# sch2.net
KiCad netlist of a schematic drawn in Altium Designer
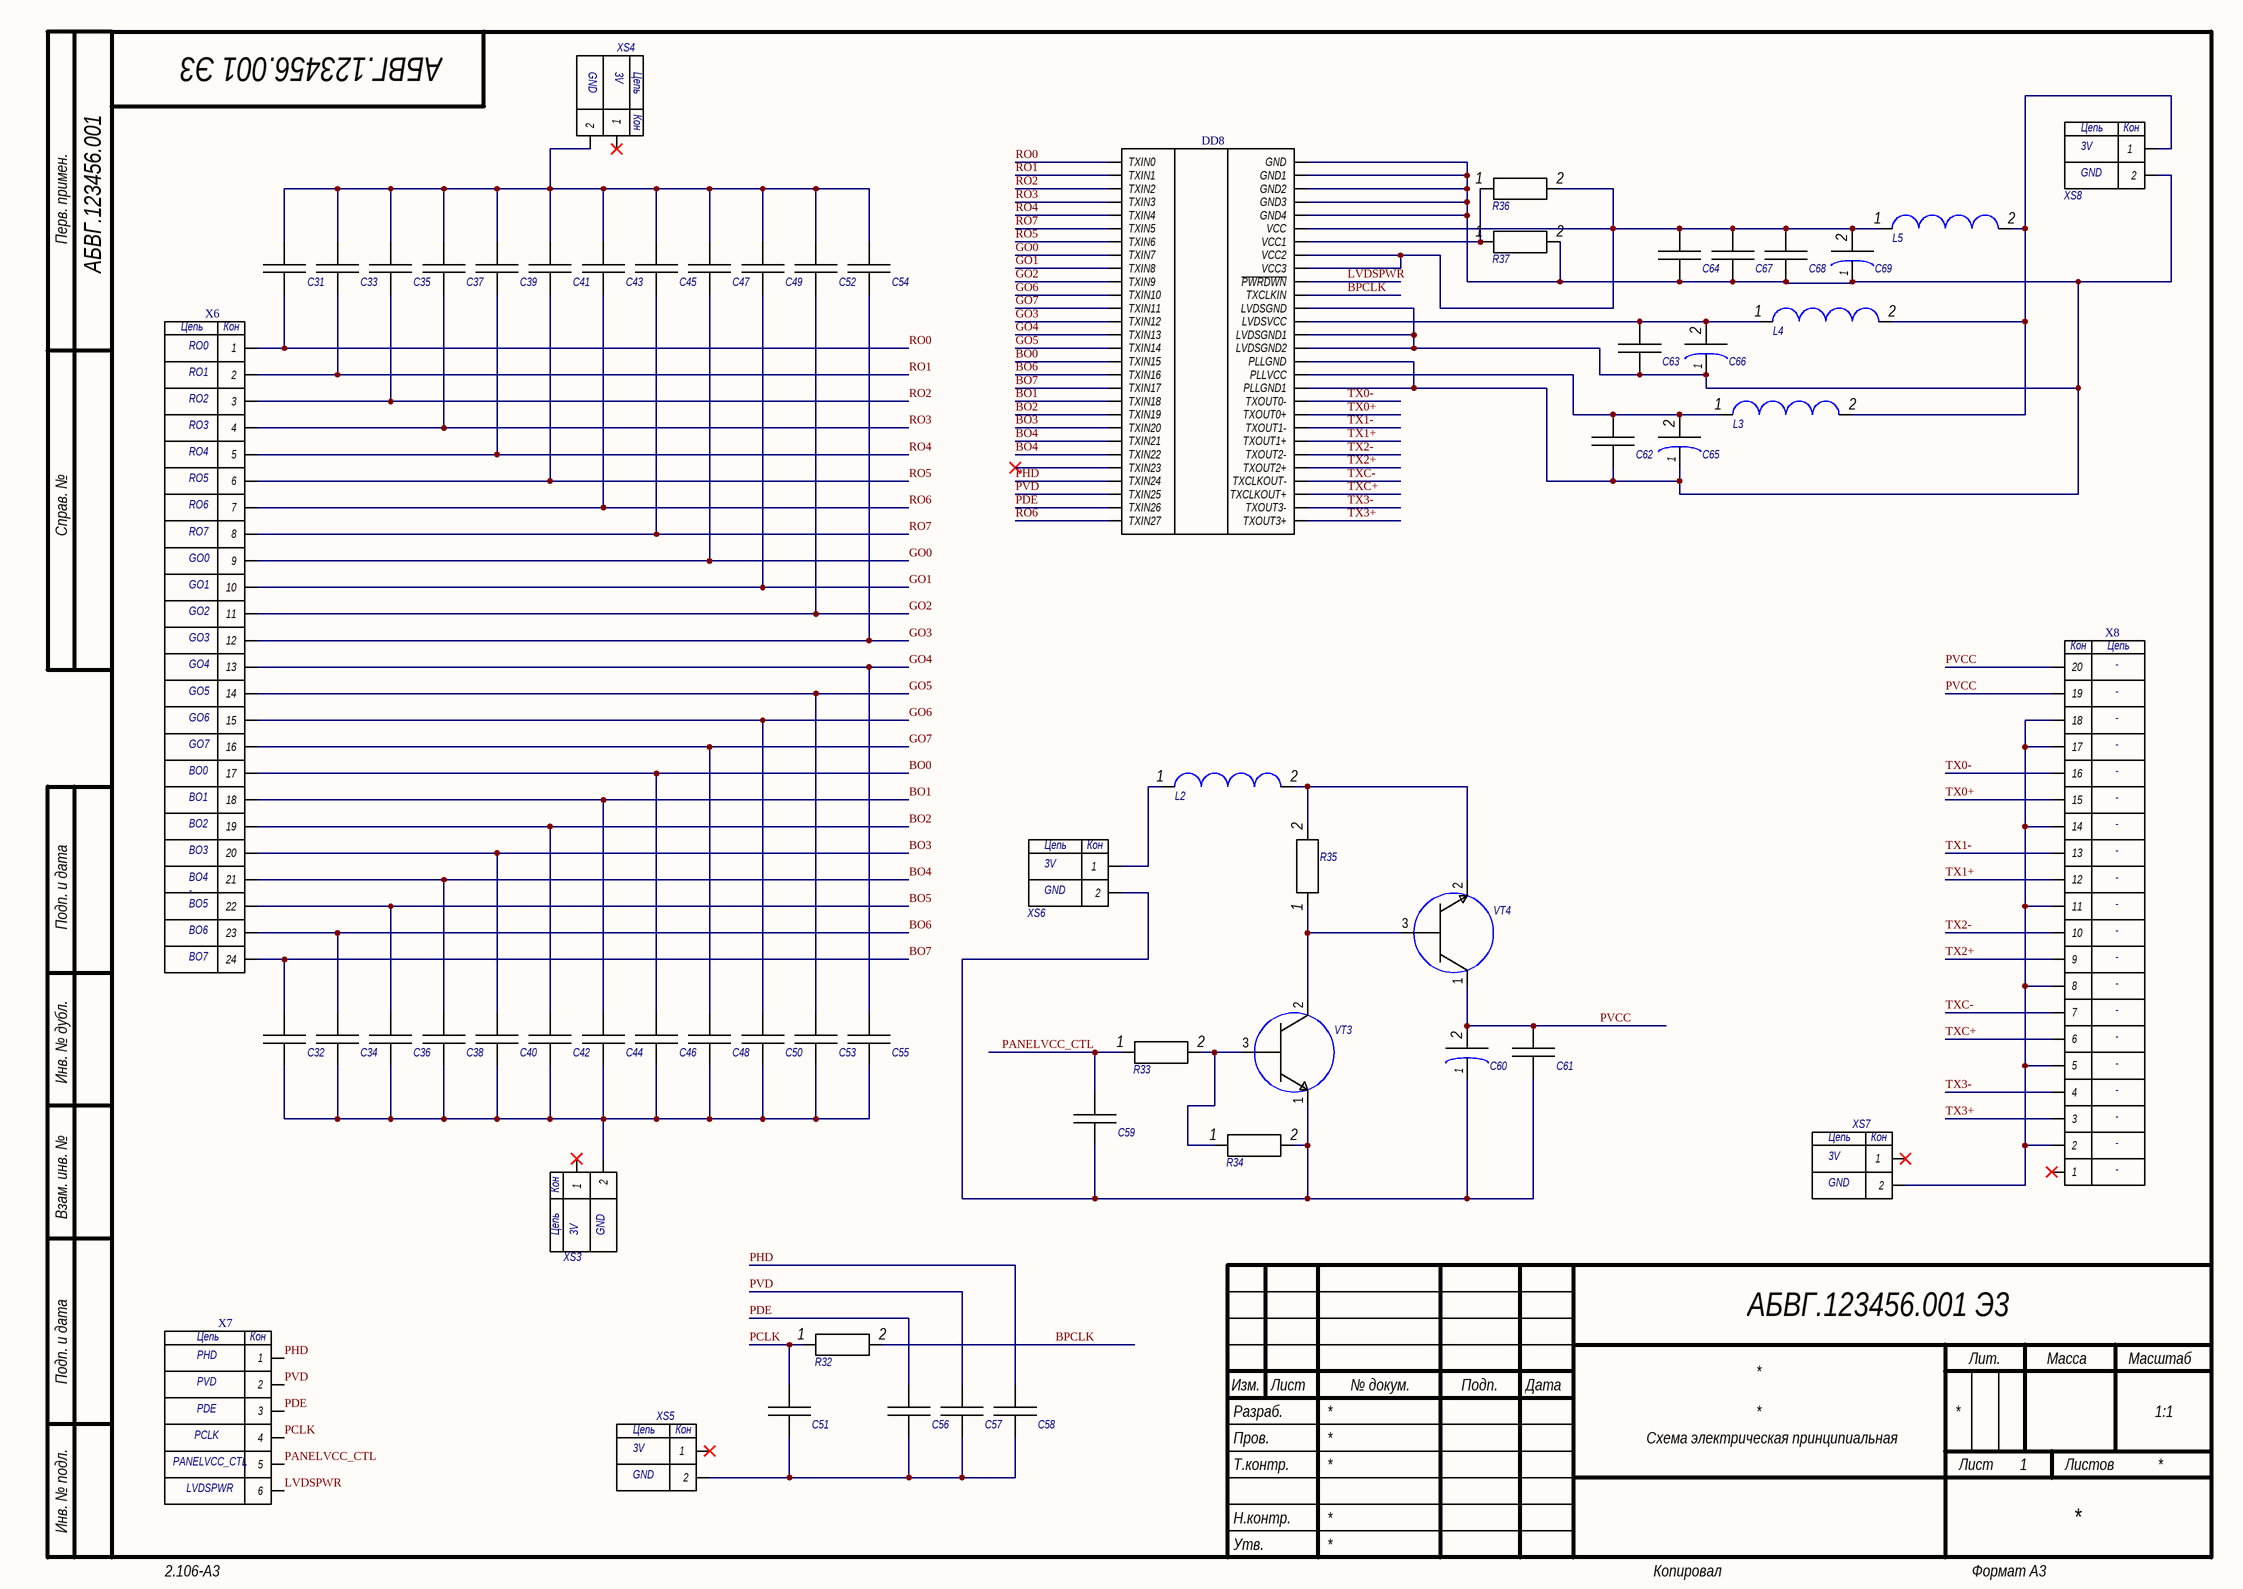
[diagram p0: sch2.SchDoc]

(export (version "E")
  (design (tool "Eeschema 10.0.6"))
  (components
    (comp (ref "C31")
      (value "Capacitor")
      (footprint "cap(0603)")
      (libsource (lib "sk7shared") (part "Capacitor"))
    )
    (comp (ref "C32")
      (value "Capacitor")
      (footprint "cap(0603)")
      (libsource (lib "sk7shared") (part "Capacitor"))
    )
    (comp (ref "C33")
      (value "Capacitor")
      (footprint "cap(0603)")
      (libsource (lib "sk7shared") (part "Capacitor"))
    )
    (comp (ref "C34")
      (value "Capacitor")
      (footprint "cap(0603)")
      (libsource (lib "sk7shared") (part "Capacitor"))
    )
    (comp (ref "C35")
      (value "Capacitor")
      (footprint "cap(0603)")
      (libsource (lib "sk7shared") (part "Capacitor"))
    )
    (comp (ref "C36")
      (value "Capacitor")
      (footprint "cap(0603)")
      (libsource (lib "sk7shared") (part "Capacitor"))
    )
    (comp (ref "C37")
      (value "Capacitor")
      (footprint "cap(0603)")
      (libsource (lib "sk7shared") (part "Capacitor"))
    )
    (comp (ref "C38")
      (value "Capacitor")
      (footprint "cap(0603)")
      (libsource (lib "sk7shared") (part "Capacitor"))
    )
    (comp (ref "C39")
      (value "Capacitor")
      (footprint "cap(0603)")
      (libsource (lib "sk7shared") (part "Capacitor"))
    )
    (comp (ref "C40")
      (value "Capacitor")
      (footprint "cap(0603)")
      (libsource (lib "sk7shared") (part "Capacitor"))
    )
    (comp (ref "C41")
      (value "Capacitor")
      (footprint "cap(0603)")
      (libsource (lib "sk7shared") (part "Capacitor"))
    )
    (comp (ref "C42")
      (value "Capacitor")
      (footprint "cap(0603)")
      (libsource (lib "sk7shared") (part "Capacitor"))
    )
    (comp (ref "C43")
      (value "Capacitor")
      (footprint "cap(0603)")
      (libsource (lib "sk7shared") (part "Capacitor"))
    )
    (comp (ref "C44")
      (value "Capacitor")
      (footprint "cap(0603)")
      (libsource (lib "sk7shared") (part "Capacitor"))
    )
    (comp (ref "C45")
      (value "Capacitor")
      (footprint "cap(0603)")
      (libsource (lib "sk7shared") (part "Capacitor"))
    )
    (comp (ref "C46")
      (value "Capacitor")
      (footprint "cap(0603)")
      (libsource (lib "sk7shared") (part "Capacitor"))
    )
    (comp (ref "C47")
      (value "Capacitor")
      (footprint "cap(0603)")
      (libsource (lib "sk7shared") (part "Capacitor"))
    )
    (comp (ref "C48")
      (value "Capacitor")
      (footprint "cap(0603)")
      (libsource (lib "sk7shared") (part "Capacitor"))
    )
    (comp (ref "C49")
      (value "Capacitor")
      (footprint "cap(0603)")
      (libsource (lib "sk7shared") (part "Capacitor"))
    )
    (comp (ref "C50")
      (value "Capacitor")
      (footprint "cap(0603)")
      (libsource (lib "sk7shared") (part "Capacitor"))
    )
    (comp (ref "C51")
      (value "Capacitor")
      (footprint "cap(0603)")
      (libsource (lib "sk7shared") (part "Capacitor"))
    )
    (comp (ref "C52")
      (value "Capacitor")
      (footprint "cap(0603)")
      (libsource (lib "sk7shared") (part "Capacitor"))
    )
    (comp (ref "C53")
      (value "Capacitor")
      (footprint "cap(0603)")
      (libsource (lib "sk7shared") (part "Capacitor"))
    )
    (comp (ref "C54")
      (value "Capacitor")
      (footprint "cap(0603)")
      (libsource (lib "sk7shared") (part "Capacitor"))
    )
    (comp (ref "C55")
      (value "Capacitor")
      (footprint "cap(0603)")
      (libsource (lib "sk7shared") (part "Capacitor"))
    )
    (comp (ref "C56")
      (value "Capacitor")
      (footprint "cap(0603)")
      (libsource (lib "sk7shared") (part "Capacitor"))
    )
    (comp (ref "C57")
      (value "Capacitor")
      (footprint "cap(0603)")
      (libsource (lib "sk7shared") (part "Capacitor"))
    )
    (comp (ref "C58")
      (value "Capacitor")
      (footprint "cap(0603)")
      (libsource (lib "sk7shared") (part "Capacitor"))
    )
    (comp (ref "C59")
      (value "Capacitor")
      (footprint "cap(0603)")
      (libsource (lib "sk7shared") (part "Capacitor"))
    )
    (comp (ref "C60")
      (value "*")
      (footprint "Capacitor 0805")
      (libsource (lib "k7shared") (part "Capacitor Duga"))
    )
    (comp (ref "C61")
      (value "Capacitor")
      (footprint "cap(0603)")
      (libsource (lib "sk7shared") (part "Capacitor"))
    )
    (comp (ref "C62")
      (value "Capacitor")
      (footprint "cap(0603)")
      (libsource (lib "sk7shared") (part "Capacitor"))
    )
    (comp (ref "C63")
      (value "Capacitor")
      (footprint "cap(0603)")
      (libsource (lib "sk7shared") (part "Capacitor"))
    )
    (comp (ref "C64")
      (value "Capacitor")
      (footprint "cap(0603)")
      (libsource (lib "sk7shared") (part "Capacitor"))
    )
    (comp (ref "C65")
      (value "*")
      (footprint "Capacitor 0805")
      (libsource (lib "k7shared") (part "Capacitor Duga"))
    )
    (comp (ref "C66")
      (value "*")
      (footprint "Capacitor 0805")
      (libsource (lib "k7shared") (part "Capacitor Duga"))
    )
    (comp (ref "C67")
      (value "Capacitor")
      (footprint "cap(0603)")
      (libsource (lib "sk7shared") (part "Capacitor"))
    )
    (comp (ref "C68")
      (value "Capacitor")
      (footprint "cap(0603)")
      (libsource (lib "sk7shared") (part "Capacitor"))
    )
    (comp (ref "C69")
      (value "*")
      (footprint "Capacitor 0805")
      (libsource (lib "k7shared") (part "Capacitor Duga"))
    )
    (comp (ref "DD8") (value "*") (footprint "THC63") (libsource (lib "k7sch2") (part "THC63")))
    (comp (ref "L2") (value "*") (footprint "Inductor 2520") (libsource (lib "k7shared") (part "Inductor")))
    (comp (ref "L3") (value "*") (footprint "Inductor 2520") (libsource (lib "k7shared") (part "Inductor")))
    (comp (ref "L4") (value "*") (footprint "Inductor 2520") (libsource (lib "k7shared") (part "Inductor")))
    (comp (ref "L5") (value "*") (footprint "Inductor 2520") (libsource (lib "k7shared") (part "Inductor")))
    (comp (ref "R32") (value "*") (footprint "Resistor 1206") (libsource (lib "k7shared") (part "Resistor")))
    (comp (ref "R33") (value "*") (footprint "Resistor 1206") (libsource (lib "k7shared") (part "Resistor")))
    (comp (ref "R34") (value "*") (footprint "Resistor 1206") (libsource (lib "k7shared") (part "Resistor")))
    (comp (ref "R35") (value "*") (footprint "Resistor 1206") (libsource (lib "k7shared") (part "Resistor")))
    (comp (ref "R36") (value "*") (footprint "Resistor 1206") (libsource (lib "k7shared") (part "Resistor")))
    (comp (ref "R37") (value "*") (footprint "Resistor 1206") (libsource (lib "k7shared") (part "Resistor")))
    (comp (ref "VT3")
      (value "*")
      (footprint "Transistor 1")
      (libsource (lib "k7shared") (part "Transistor 1"))
    )
    (comp (ref "VT4")
      (value "*")
      (footprint "Transistor 1")
      (libsource (lib "k7shared") (part "Transistor 2_1"))
    )
    (comp (ref "X6") (value "*") (footprint "BUSES") (libsource (lib "k7sch2") (part "BUSES")))
    (comp (ref "X7") (value "*") (footprint "Inputs") (libsource (lib "k7sch2") (part "Inputs")))
    (comp (ref "X8") (value "*") (footprint "DF14A") (libsource (lib "k7sch2") (part "DF14A")))
    (comp (ref "XS3") (value "*") (footprint "VCC-GND") (libsource (lib "k7shared") (part "VCC-GND R")))
    (comp (ref "XS4") (value "*") (footprint "VCC-GND") (libsource (lib "k7shared") (part "VCC-GND R")))
    (comp (ref "XS5") (value "*") (footprint "VCC-GND") (libsource (lib "k7shared") (part "VCC-GND R")))
    (comp (ref "XS6") (value "*") (footprint "VCC-GND") (libsource (lib "k7shared") (part "VCC-GND R")))
    (comp (ref "XS7") (value "*") (footprint "VCC-GND") (libsource (lib "k7shared") (part "VCC-GND R")))
    (comp (ref "XS8") (value "*") (footprint "VCC-GND") (libsource (lib "k7shared") (part "VCC-GND R")))
  )
  (nets
    (net (code "1") (name "/BO0") (class "Default")
      (node (ref "C46") (pin "2") (pinfunction "2_2") (pintype "passive"))
      (node (ref "DD8") (pin "16") (pinfunction "TXIN15_16") (pintype "passive"))
      (node (ref "X6") (pin "17") (pinfunction "17_17") (pintype "passive"))
    )
    (net (code "2") (name "/BO1") (class "Default")
      (node (ref "C44") (pin "2") (pinfunction "2_2") (pintype "passive"))
      (node (ref "DD8") (pin "19") (pinfunction "TXIN18_19") (pintype "passive"))
      (node (ref "X6") (pin "18") (pinfunction "18_18") (pintype "passive"))
    )
    (net (code "3") (name "/BO2") (class "Default")
      (node (ref "C42") (pin "2") (pinfunction "2_2") (pintype "passive"))
      (node (ref "DD8") (pin "20") (pinfunction "TXIN19_20") (pintype "passive"))
      (node (ref "X6") (pin "19") (pinfunction "19_19") (pintype "passive"))
    )
    (net (code "4") (name "/BO3") (class "Default")
      (node (ref "C40") (pin "2") (pinfunction "2_2") (pintype "passive"))
      (node (ref "DD8") (pin "21") (pinfunction "TXIN20_21") (pintype "passive"))
      (node (ref "X6") (pin "20") (pinfunction "20_20") (pintype "passive"))
    )
    (net (code "5") (name "/BO4") (class "Default")
      (node (ref "C38") (pin "2") (pinfunction "2_2") (pintype "passive"))
      (node (ref "DD8") (pin "22") (pinfunction "TXIN21_22") (pintype "passive"))
      (node (ref "DD8") (pin "23") (pinfunction "TXIN22_23") (pintype "passive"))
      (node (ref "X6") (pin "21") (pinfunction "21_21") (pintype "passive"))
    )
    (net (code "6") (name "/BO5") (class "Default")
      (node (ref "C36") (pin "2") (pinfunction "2_2") (pintype "passive"))
      (node (ref "X6") (pin "22") (pinfunction "22_22") (pintype "passive"))
    )
    (net (code "7") (name "/BO6") (class "Default")
      (node (ref "C34") (pin "2") (pinfunction "2_2") (pintype "passive"))
      (node (ref "DD8") (pin "17") (pinfunction "TXIN16_17") (pintype "passive"))
      (node (ref "X6") (pin "23") (pinfunction "23_23") (pintype "passive"))
    )
    (net (code "8") (name "/BO7") (class "Default")
      (node (ref "C32") (pin "2") (pinfunction "2_2") (pintype "passive"))
      (node (ref "DD8") (pin "18") (pinfunction "TXIN17_18") (pintype "passive"))
      (node (ref "X6") (pin "24") (pinfunction "24_24") (pintype "passive"))
    )
    (net (code "9") (name "/BPCLK") (class "Default")
      (node (ref "DD8") (pin "46") (pinfunction "TXCLKIN_46") (pintype "passive"))
      (node (ref "R32") (pin "2") (pinfunction "2_2") (pintype "passive"))
    )
    (net (code "10") (name "/GO0") (class "Default")
      (node (ref "C47") (pin "1") (pinfunction "1_1") (pintype "passive"))
      (node (ref "DD8") (pin "8") (pinfunction "TXIN7_8") (pintype "passive"))
      (node (ref "X6") (pin "9") (pinfunction "9_9") (pintype "passive"))
    )
    (net (code "11") (name "/GO1") (class "Default")
      (node (ref "C49") (pin "1") (pinfunction "1_1") (pintype "passive"))
      (node (ref "DD8") (pin "9") (pinfunction "TXIN8_9") (pintype "passive"))
      (node (ref "X6") (pin "10") (pinfunction "10_10") (pintype "passive"))
    )
    (net (code "12") (name "/GO2") (class "Default")
      (node (ref "C52") (pin "1") (pinfunction "1_1") (pintype "passive"))
      (node (ref "DD8") (pin "10") (pinfunction "TXIN9_10") (pintype "passive"))
      (node (ref "X6") (pin "11") (pinfunction "11_11") (pintype "passive"))
    )
    (net (code "13") (name "/GO3") (class "Default")
      (node (ref "C54") (pin "1") (pinfunction "1_1") (pintype "passive"))
      (node (ref "DD8") (pin "13") (pinfunction "TXIN12_13") (pintype "passive"))
      (node (ref "X6") (pin "12") (pinfunction "12_12") (pintype "passive"))
    )
    (net (code "14") (name "/GO4") (class "Default")
      (node (ref "C55") (pin "2") (pinfunction "2_2") (pintype "passive"))
      (node (ref "DD8") (pin "14") (pinfunction "TXIN13_14") (pintype "passive"))
      (node (ref "X6") (pin "13") (pinfunction "13_13") (pintype "passive"))
    )
    (net (code "15") (name "/GO5") (class "Default")
      (node (ref "C53") (pin "2") (pinfunction "2_2") (pintype "passive"))
      (node (ref "DD8") (pin "15") (pinfunction "TXIN14_15") (pintype "passive"))
      (node (ref "X6") (pin "14") (pinfunction "14_14") (pintype "passive"))
    )
    (net (code "16") (name "/GO6") (class "Default")
      (node (ref "C50") (pin "2") (pinfunction "2_2") (pintype "passive"))
      (node (ref "DD8") (pin "11") (pinfunction "TXIN10_11") (pintype "passive"))
      (node (ref "X6") (pin "15") (pinfunction "15_15") (pintype "passive"))
    )
    (net (code "17") (name "/GO7") (class "Default")
      (node (ref "C48") (pin "2") (pinfunction "2_2") (pintype "passive"))
      (node (ref "DD8") (pin "12") (pinfunction "TXIN11_12") (pintype "passive"))
      (node (ref "X6") (pin "16") (pinfunction "16_16") (pintype "passive"))
    )
    (net (code "18") (name "/LVDSPWR") (class "Default")
      (node (ref "DD8") (pin "47") (pinfunction "~{PWRDWN}_47") (pintype "passive"))
      (node (ref "X7") (pin "6") (pinfunction "6_6") (pintype "passive"))
    )
    (net (code "19") (name "/PANELVCC_CTL") (class "Default")
      (node (ref "C59") (pin "2") (pinfunction "2_2") (pintype "passive"))
      (node (ref "R33") (pin "1") (pinfunction "1_1") (pintype "passive"))
      (node (ref "X7") (pin "5") (pinfunction "5_5") (pintype "passive"))
    )
    (net (code "20") (name "/PCLK") (class "Default")
      (node (ref "C51") (pin "2") (pinfunction "2_2") (pintype "passive"))
      (node (ref "R32") (pin "1") (pinfunction "1_1") (pintype "passive"))
      (node (ref "X7") (pin "4") (pinfunction "4_4") (pintype "passive"))
    )
    (net (code "21") (name "/PDE") (class "Default")
      (node (ref "C56") (pin "2") (pinfunction "2_2") (pintype "passive"))
      (node (ref "DD8") (pin "27") (pinfunction "TXIN26_27") (pintype "passive"))
      (node (ref "X7") (pin "3") (pinfunction "3_3") (pintype "passive"))
    )
    (net (code "22") (name "/PHD") (class "Default")
      (node (ref "C58") (pin "2") (pinfunction "2_2") (pintype "passive"))
      (node (ref "DD8") (pin "25") (pinfunction "TXIN24_25") (pintype "passive"))
      (node (ref "X7") (pin "1") (pinfunction "1_1") (pintype "passive"))
    )
    (net (code "23") (name "/PVCC") (class "Default")
      (node (ref "C60") (pin "2") (pinfunction "2_2") (pintype "passive"))
      (node (ref "C61") (pin "2") (pinfunction "2_2") (pintype "passive"))
      (node (ref "VT4") (pin "1") (pinfunction "KOLLECTOR_1") (pintype "passive"))
      (node (ref "X8") (pin "19") (pinfunction "19_19") (pintype "passive"))
      (node (ref "X8") (pin "20") (pinfunction "20_20") (pintype "passive"))
    )
    (net (code "24") (name "/PVD") (class "Default")
      (node (ref "C57") (pin "2") (pinfunction "2_2") (pintype "passive"))
      (node (ref "DD8") (pin "26") (pinfunction "TXIN25_26") (pintype "passive"))
      (node (ref "X7") (pin "2") (pinfunction "2_2") (pintype "passive"))
    )
    (net (code "25") (name "/RO0") (class "Default")
      (node (ref "C31") (pin "1") (pinfunction "1_1") (pintype "passive"))
      (node (ref "DD8") (pin "1") (pinfunction "TXIN0_1") (pintype "passive"))
      (node (ref "X6") (pin "1") (pinfunction "1_1") (pintype "passive"))
    )
    (net (code "26") (name "/RO1") (class "Default")
      (node (ref "C33") (pin "1") (pinfunction "1_1") (pintype "passive"))
      (node (ref "DD8") (pin "2") (pinfunction "TXIN1_2") (pintype "passive"))
      (node (ref "X6") (pin "2") (pinfunction "2_2") (pintype "passive"))
    )
    (net (code "27") (name "/RO2") (class "Default")
      (node (ref "C35") (pin "1") (pinfunction "1_1") (pintype "passive"))
      (node (ref "DD8") (pin "3") (pinfunction "TXIN2_3") (pintype "passive"))
      (node (ref "X6") (pin "3") (pinfunction "3_3") (pintype "passive"))
    )
    (net (code "28") (name "/RO3") (class "Default")
      (node (ref "C37") (pin "1") (pinfunction "1_1") (pintype "passive"))
      (node (ref "DD8") (pin "4") (pinfunction "TXIN3_4") (pintype "passive"))
      (node (ref "X6") (pin "4") (pinfunction "4_4") (pintype "passive"))
    )
    (net (code "29") (name "/RO4") (class "Default")
      (node (ref "C39") (pin "1") (pinfunction "1_1") (pintype "passive"))
      (node (ref "DD8") (pin "5") (pinfunction "TXIN4_5") (pintype "passive"))
      (node (ref "X6") (pin "5") (pinfunction "5_5") (pintype "passive"))
    )
    (net (code "30") (name "/RO5") (class "Default")
      (node (ref "C41") (pin "1") (pinfunction "1_1") (pintype "passive"))
      (node (ref "DD8") (pin "7") (pinfunction "TXIN6_7") (pintype "passive"))
      (node (ref "X6") (pin "6") (pinfunction "6_6") (pintype "passive"))
    )
    (net (code "31") (name "/RO6") (class "Default")
      (node (ref "C43") (pin "1") (pinfunction "1_1") (pintype "passive"))
      (node (ref "DD8") (pin "28") (pinfunction "TXIN27_28") (pintype "passive"))
      (node (ref "X6") (pin "7") (pinfunction "7_7") (pintype "passive"))
    )
    (net (code "32") (name "/RO7") (class "Default")
      (node (ref "C45") (pin "1") (pinfunction "1_1") (pintype "passive"))
      (node (ref "DD8") (pin "6") (pinfunction "TXIN5_6") (pintype "passive"))
      (node (ref "X6") (pin "8") (pinfunction "8_8") (pintype "passive"))
    )
    (net (code "33") (name "/TX0+") (class "Default")
      (node (ref "DD8") (pin "37") (pinfunction "TXOUT0+_37") (pintype "passive"))
      (node (ref "X8") (pin "15") (pinfunction "15_15") (pintype "passive"))
    )
    (net (code "34") (name "/TX0-") (class "Default")
      (node (ref "DD8") (pin "38") (pinfunction "TXOUT0-_38") (pintype "passive"))
      (node (ref "X8") (pin "16") (pinfunction "16_16") (pintype "passive"))
    )
    (net (code "35") (name "/TX1+") (class "Default")
      (node (ref "DD8") (pin "35") (pinfunction "TXOUT1+_35") (pintype "passive"))
      (node (ref "X8") (pin "12") (pinfunction "12_12") (pintype "passive"))
    )
    (net (code "36") (name "/TX1-") (class "Default")
      (node (ref "DD8") (pin "36") (pinfunction "TXOUT1-_36") (pintype "passive"))
      (node (ref "X8") (pin "13") (pinfunction "13_13") (pintype "passive"))
    )
    (net (code "37") (name "/TX2+") (class "Default")
      (node (ref "DD8") (pin "33") (pinfunction "TXOUT2+_33") (pintype "passive"))
      (node (ref "X8") (pin "9") (pinfunction "9_9") (pintype "passive"))
    )
    (net (code "38") (name "/TX2-") (class "Default")
      (node (ref "DD8") (pin "34") (pinfunction "TXOUT2-_34") (pintype "passive"))
      (node (ref "X8") (pin "10") (pinfunction "10_10") (pintype "passive"))
    )
    (net (code "39") (name "/TX3+") (class "Default")
      (node (ref "DD8") (pin "29") (pinfunction "TXOUT3+_29") (pintype "passive"))
      (node (ref "X8") (pin "3") (pinfunction "3_3") (pintype "passive"))
    )
    (net (code "40") (name "/TX3-") (class "Default")
      (node (ref "DD8") (pin "30") (pinfunction "TXOUT3-_30") (pintype "passive"))
      (node (ref "X8") (pin "4") (pinfunction "4_4") (pintype "passive"))
    )
    (net (code "41") (name "/TXC+") (class "Default")
      (node (ref "DD8") (pin "31") (pinfunction "TXCLKOUT+_31") (pintype "passive"))
      (node (ref "X8") (pin "6") (pinfunction "6_6") (pintype "passive"))
    )
    (net (code "42") (name "/TXC-") (class "Default")
      (node (ref "DD8") (pin "32") (pinfunction "TXCLKOUT-_32") (pintype "passive"))
      (node (ref "X8") (pin "7") (pinfunction "7_7") (pintype "passive"))
    )
    (net (code "43") (name "Net-(C31-Pad2)") (class "Default")
      (node (ref "C31") (pin "2") (pinfunction "2_2") (pintype "passive"))
      (node (ref "C33") (pin "2") (pinfunction "2_2") (pintype "passive"))
      (node (ref "C35") (pin "2") (pinfunction "2_2") (pintype "passive"))
      (node (ref "C37") (pin "2") (pinfunction "2_2") (pintype "passive"))
      (node (ref "C39") (pin "2") (pinfunction "2_2") (pintype "passive"))
      (node (ref "C41") (pin "2") (pinfunction "2_2") (pintype "passive"))
      (node (ref "C43") (pin "2") (pinfunction "2_2") (pintype "passive"))
      (node (ref "C45") (pin "2") (pinfunction "2_2") (pintype "passive"))
      (node (ref "C47") (pin "2") (pinfunction "2_2") (pintype "passive"))
      (node (ref "C49") (pin "2") (pinfunction "2_2") (pintype "passive"))
      (node (ref "C52") (pin "2") (pinfunction "2_2") (pintype "passive"))
      (node (ref "C54") (pin "2") (pinfunction "2_2") (pintype "passive"))
      (node (ref "XS4") (pin "2") (pinfunction "2_2") (pintype "passive"))
    )
    (net (code "44") (name "Net-(C32-Pad1)") (class "Default")
      (node (ref "C32") (pin "1") (pinfunction "1_1") (pintype "passive"))
      (node (ref "C34") (pin "1") (pinfunction "1_1") (pintype "passive"))
      (node (ref "C36") (pin "1") (pinfunction "1_1") (pintype "passive"))
      (node (ref "C38") (pin "1") (pinfunction "1_1") (pintype "passive"))
      (node (ref "C40") (pin "1") (pinfunction "1_1") (pintype "passive"))
      (node (ref "C42") (pin "1") (pinfunction "1_1") (pintype "passive"))
      (node (ref "C44") (pin "1") (pinfunction "1_1") (pintype "passive"))
      (node (ref "C46") (pin "1") (pinfunction "1_1") (pintype "passive"))
      (node (ref "C48") (pin "1") (pinfunction "1_1") (pintype "passive"))
      (node (ref "C50") (pin "1") (pinfunction "1_1") (pintype "passive"))
      (node (ref "C53") (pin "1") (pinfunction "1_1") (pintype "passive"))
      (node (ref "C55") (pin "1") (pinfunction "1_1") (pintype "passive"))
      (node (ref "XS3") (pin "2") (pinfunction "2_2") (pintype "passive"))
    )
    (net (code "45") (name "Net-(C51-Pad1)") (class "Default")
      (node (ref "C51") (pin "1") (pinfunction "1_1") (pintype "passive"))
      (node (ref "C56") (pin "1") (pinfunction "1_1") (pintype "passive"))
      (node (ref "C57") (pin "1") (pinfunction "1_1") (pintype "passive"))
      (node (ref "C58") (pin "1") (pinfunction "1_1") (pintype "passive"))
      (node (ref "XS5") (pin "2") (pinfunction "2_2") (pintype "passive"))
    )
    (net (code "46") (name "Net-(DD8-GND)") (class "Default")
      (node (ref "C62") (pin "1") (pinfunction "1_1") (pintype "passive"))
      (node (ref "C63") (pin "1") (pinfunction "1_1") (pintype "passive"))
      (node (ref "C64") (pin "1") (pinfunction "1_1") (pintype "passive"))
      (node (ref "C65") (pin "1") (pinfunction "1_1") (pintype "passive"))
      (node (ref "C66") (pin "1") (pinfunction "1_1") (pintype "passive"))
      (node (ref "C67") (pin "1") (pinfunction "1_1") (pintype "passive"))
      (node (ref "C68") (pin "1") (pinfunction "1_1") (pintype "passive"))
      (node (ref "C69") (pin "1") (pinfunction "1_1") (pintype "passive"))
      (node (ref "DD8") (pin "39") (pinfunction "PLLGND1_39") (pintype "passive"))
      (node (ref "DD8") (pin "41") (pinfunction "PLLGND_41") (pintype "passive"))
      (node (ref "DD8") (pin "42") (pinfunction "LVDSGND2_42") (pintype "passive"))
      (node (ref "DD8") (pin "43") (pinfunction "LVDSGND1_43") (pintype "passive"))
      (node (ref "DD8") (pin "45") (pinfunction "LVDSGND_45") (pintype "passive"))
      (node (ref "DD8") (pin "52") (pinfunction "GND4_52") (pintype "passive"))
      (node (ref "DD8") (pin "53") (pinfunction "GND3_53") (pintype "passive"))
      (node (ref "DD8") (pin "54") (pinfunction "GND2_54") (pintype "passive"))
      (node (ref "DD8") (pin "55") (pinfunction "GND1_55") (pintype "passive"))
      (node (ref "DD8") (pin "56") (pinfunction "GND_56") (pintype "passive"))
      (node (ref "R37") (pin "2") (pinfunction "2_2") (pintype "passive"))
      (node (ref "XS8") (pin "2") (pinfunction "2_2") (pintype "passive"))
    )
    (net (code "47") (name "Net-(DD8-LVDSVCC)") (class "Default")
      (node (ref "C63") (pin "2") (pinfunction "2_2") (pintype "passive"))
      (node (ref "C66") (pin "2") (pinfunction "2_2") (pintype "passive"))
      (node (ref "DD8") (pin "44") (pinfunction "LVDSVCC_44") (pintype "passive"))
      (node (ref "L4") (pin "1") (pinfunction "1_1") (pintype "passive"))
    )
    (net (code "48") (name "Net-(DD8-PLLVCC)") (class "Default")
      (node (ref "C62") (pin "2") (pinfunction "2_2") (pintype "passive"))
      (node (ref "C65") (pin "2") (pinfunction "2_2") (pintype "passive"))
      (node (ref "DD8") (pin "40") (pinfunction "PLLVCC_40") (pintype "passive"))
      (node (ref "L3") (pin "1") (pinfunction "1_1") (pintype "passive"))
    )
    (net (code "49") (name "Net-(DD8-VCC)") (class "Default")
      (node (ref "C64") (pin "2") (pinfunction "2_2") (pintype "passive"))
      (node (ref "C67") (pin "2") (pinfunction "2_2") (pintype "passive"))
      (node (ref "C68") (pin "2") (pinfunction "2_2") (pintype "passive"))
      (node (ref "C69") (pin "2") (pinfunction "2_2") (pintype "passive"))
      (node (ref "DD8") (pin "48") (pinfunction "VCC3_48") (pintype "passive"))
      (node (ref "DD8") (pin "49") (pinfunction "VCC2_49") (pintype "passive"))
      (node (ref "DD8") (pin "51") (pinfunction "VCC_51") (pintype "passive"))
      (node (ref "L5") (pin "1") (pinfunction "1_1") (pintype "passive"))
      (node (ref "R36") (pin "2") (pinfunction "2_2") (pintype "passive"))
    )
    (net (code "50") (name "Net-(DD8-VCC1)") (class "Default")
      (node (ref "DD8") (pin "50") (pinfunction "VCC1_50") (pintype "passive"))
      (node (ref "R36") (pin "1") (pinfunction "1_1") (pintype "passive"))
      (node (ref "R37") (pin "1") (pinfunction "1_1") (pintype "passive"))
    )
    (net (code "51") (name "Net-(L2-Pad1)") (class "Default")
      (node (ref "L2") (pin "1") (pinfunction "1_1") (pintype "passive"))
      (node (ref "XS6") (pin "1") (pinfunction "1_1") (pintype "passive"))
    )
    (net (code "52") (name "Net-(L3-Pad2)") (class "Default")
      (node (ref "L3") (pin "2") (pinfunction "2_2") (pintype "passive"))
      (node (ref "L4") (pin "2") (pinfunction "2_2") (pintype "passive"))
      (node (ref "L5") (pin "2") (pinfunction "2_2") (pintype "passive"))
      (node (ref "XS8") (pin "1") (pinfunction "1_1") (pintype "passive"))
    )
    (net (code "53") (name "Net-(VT3-BAZA)") (class "Default")
      (node (ref "R33") (pin "2") (pinfunction "2_2") (pintype "passive"))
      (node (ref "R34") (pin "1") (pinfunction "1_1") (pintype "passive"))
      (node (ref "VT3") (pin "3") (pinfunction "BAZA_3") (pintype "passive"))
    )
    (net (code "54") (name "Net-(VT3-EMITTER)") (class "Default")
      (node (ref "R35") (pin "1") (pinfunction "1_1") (pintype "passive"))
      (node (ref "VT3") (pin "2") (pinfunction "EMITTER_2") (pintype "passive"))
      (node (ref "VT4") (pin "3") (pinfunction "BAZA_3") (pintype "passive"))
    )
    (net (code "55") (name "Net-(VT3-KOLLECTOR)") (class "Default")
      (node (ref "C59") (pin "1") (pinfunction "1_1") (pintype "passive"))
      (node (ref "C60") (pin "1") (pinfunction "1_1") (pintype "passive"))
      (node (ref "C61") (pin "1") (pinfunction "1_1") (pintype "passive"))
      (node (ref "R34") (pin "2") (pinfunction "2_2") (pintype "passive"))
      (node (ref "VT3") (pin "1") (pinfunction "KOLLECTOR_1") (pintype "passive"))
      (node (ref "XS6") (pin "2") (pinfunction "2_2") (pintype "passive"))
    )
    (net (code "56") (name "Net-(VT4-EMITTER)") (class "Default")
      (node (ref "L2") (pin "2") (pinfunction "2_2") (pintype "passive"))
      (node (ref "R35") (pin "2") (pinfunction "2_2") (pintype "passive"))
      (node (ref "VT4") (pin "2") (pinfunction "EMITTER_2") (pintype "passive"))
    )
    (net (code "57") (name "Net-(X8-Pad11)") (class "Default")
      (node (ref "X8") (pin "11") (pinfunction "11_11") (pintype "passive"))
      (node (ref "X8") (pin "14") (pinfunction "14_14") (pintype "passive"))
      (node (ref "X8") (pin "17") (pinfunction "17_17") (pintype "passive"))
      (node (ref "X8") (pin "18") (pinfunction "18_18") (pintype "passive"))
      (node (ref "X8") (pin "2") (pinfunction "2_2") (pintype "passive"))
      (node (ref "X8") (pin "5") (pinfunction "5_5") (pintype "passive"))
      (node (ref "X8") (pin "8") (pinfunction "8_8") (pintype "passive"))
      (node (ref "XS7") (pin "2") (pinfunction "2_2") (pintype "passive"))
    )
    (net (code "58") (name "unconnected-(DD8-TXIN23-Pad24)") (class "Default")
      (node (ref "DD8") (pin "24") (pinfunction "TXIN23_24") (pintype "passive+no_connect"))
    )
    (net (code "59") (name "unconnected-(X8-Pad1)") (class "Default")
      (node (ref "X8") (pin "1") (pinfunction "1_1") (pintype "passive+no_connect"))
    )
    (net (code "60") (name "unconnected-(XS3-Pad1)") (class "Default")
      (node (ref "XS3") (pin "1") (pinfunction "1_1") (pintype "passive+no_connect"))
    )
    (net (code "61") (name "unconnected-(XS4-Pad1)") (class "Default")
      (node (ref "XS4") (pin "1") (pinfunction "1_1") (pintype "passive+no_connect"))
    )
    (net (code "62") (name "unconnected-(XS5-Pad1)") (class "Default")
      (node (ref "XS5") (pin "1") (pinfunction "1_1") (pintype "passive+no_connect"))
    )
    (net (code "63") (name "unconnected-(XS7-Pad1)") (class "Default")
      (node (ref "XS7") (pin "1") (pinfunction "1_1") (pintype "passive+no_connect"))
    )
  )
)
